# Sheet.net
KiCad netlist of a schematic drawn in Altium Designer
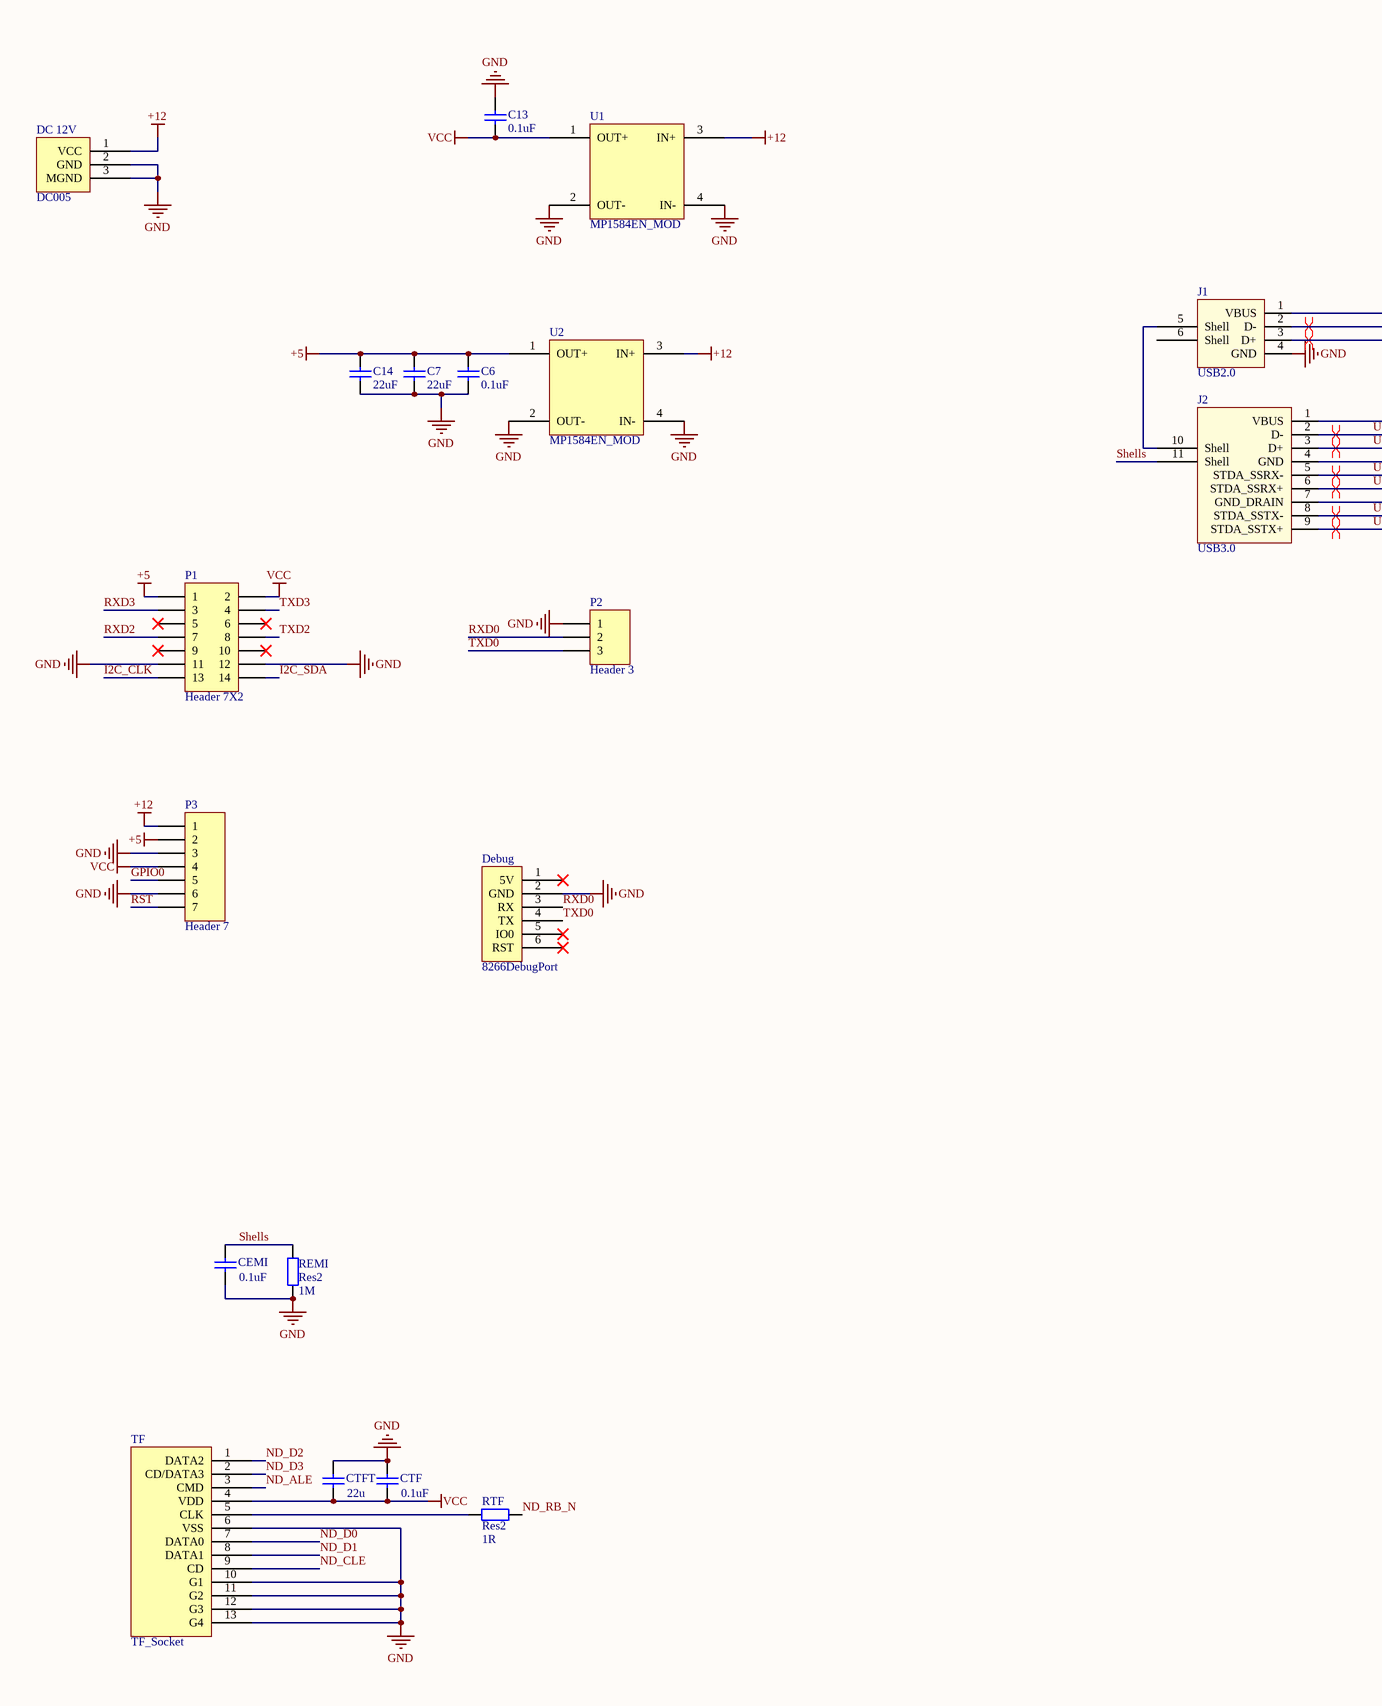
[diagram p0: Sheet.SchDoc, left]
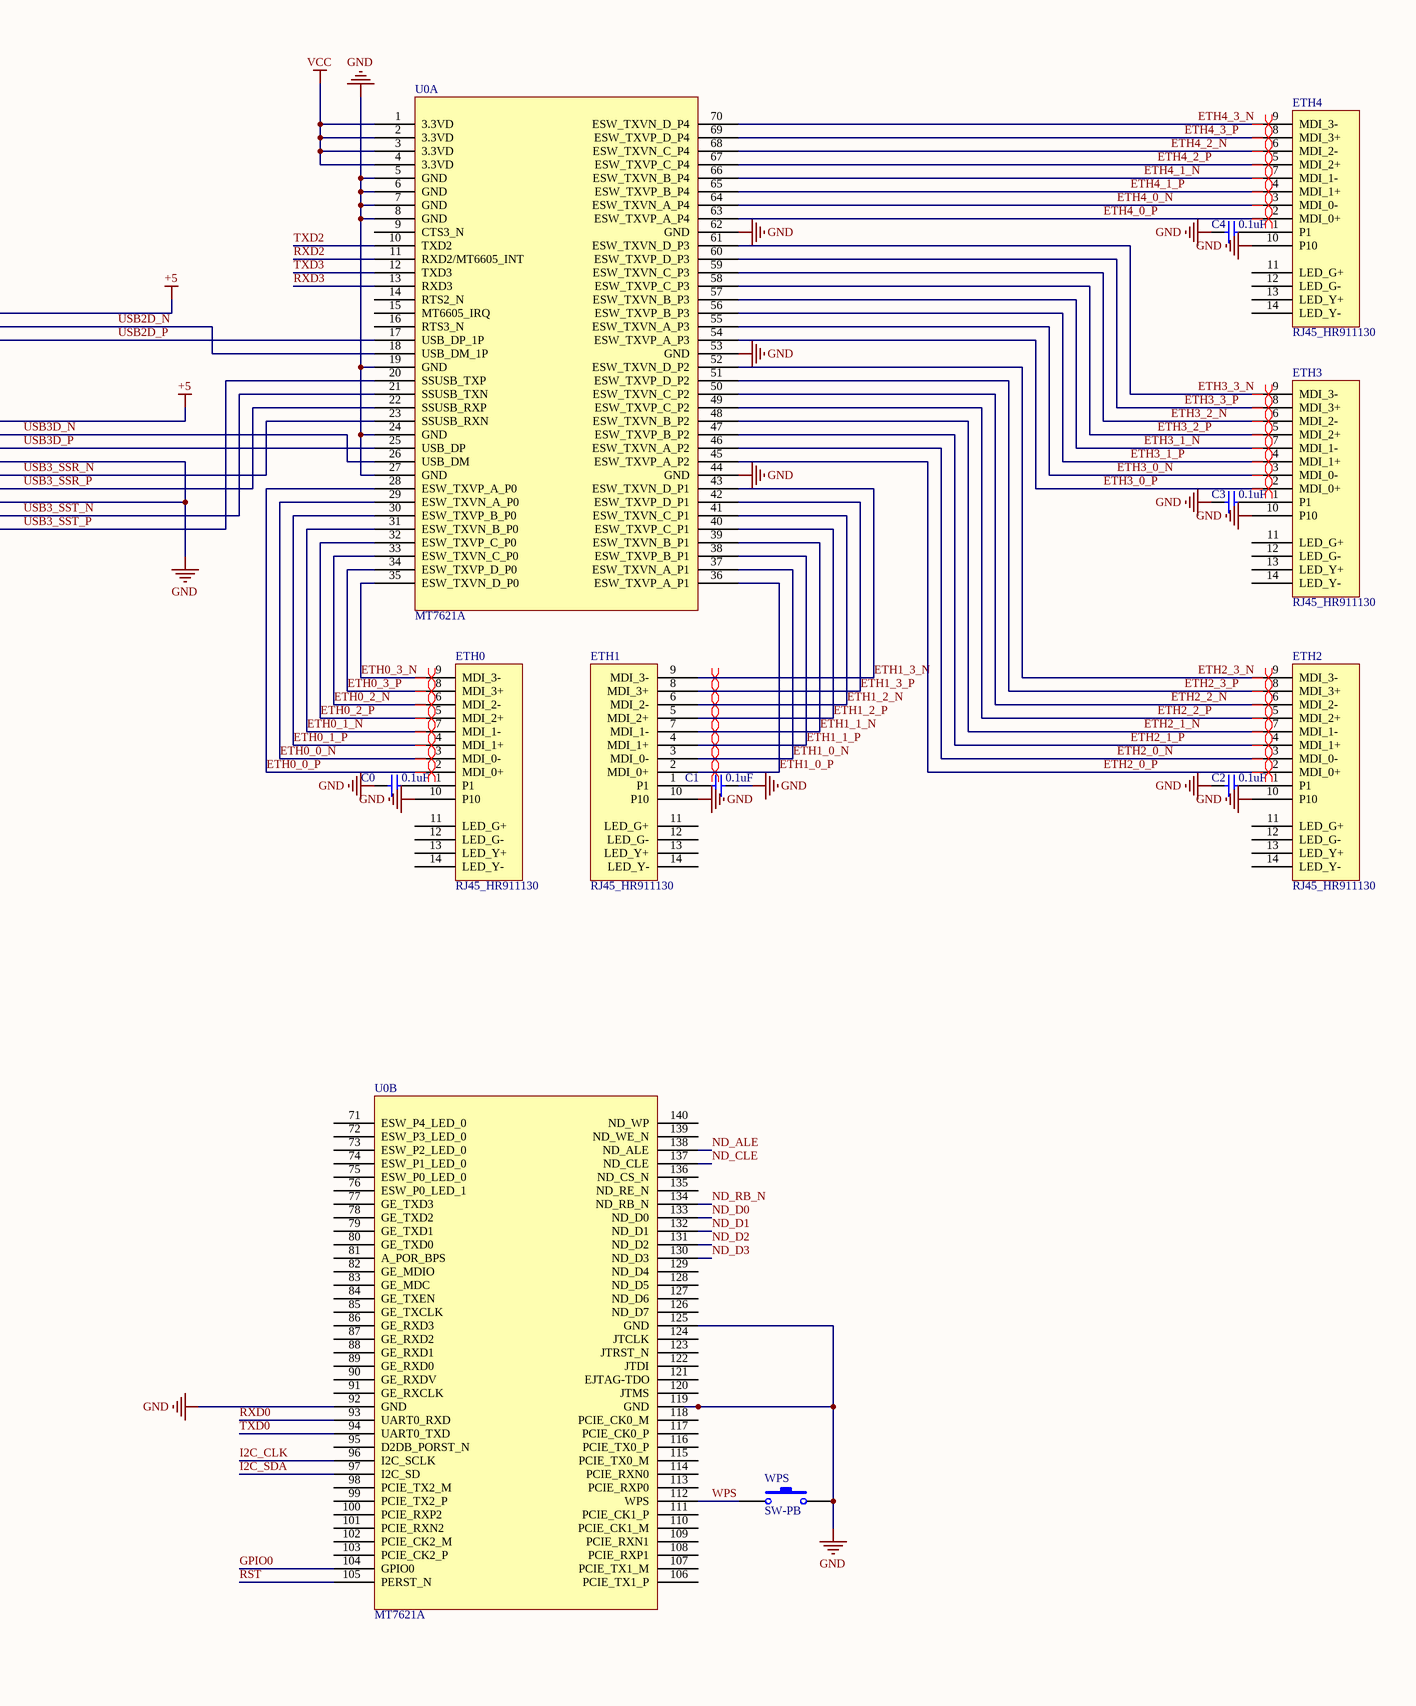
[diagram p1: Sheet.SchDoc, right]

(export (version "E")
  (design (tool "Eeschema 10.0.6"))
  (components
    (comp (ref "C0")
      (value "0.1uF")
      (footprint "My1206")
      (description "Capacitor")
      (fields (field (name "Comment") "Cap") (field (name "PUBLISHER") "Altium Limited"))
      (libsource (lib "Miscellaneous Devices") (part "Cap"))
    )
    (comp (ref "C1")
      (value "0.1uF")
      (footprint "My1206")
      (description "Capacitor")
      (fields (field (name "Comment") "Cap") (field (name "PUBLISHER") "Altium Limited"))
      (libsource (lib "Miscellaneous Devices") (part "Cap"))
    )
    (comp (ref "C2")
      (value "0.1uF")
      (footprint "My1206")
      (description "Capacitor")
      (fields (field (name "Comment") "Cap") (field (name "PUBLISHER") "Altium Limited"))
      (libsource (lib "Miscellaneous Devices") (part "Cap"))
    )
    (comp (ref "C3")
      (value "0.1uF")
      (footprint "My1206")
      (description "Capacitor")
      (fields (field (name "Comment") "Cap") (field (name "PUBLISHER") "Altium Limited"))
      (libsource (lib "Miscellaneous Devices") (part "Cap"))
    )
    (comp (ref "C4")
      (value "0.1uF")
      (footprint "My1206")
      (description "Capacitor")
      (fields (field (name "Comment") "Cap") (field (name "PUBLISHER") "Altium Limited"))
      (libsource (lib "Miscellaneous Devices") (part "Cap"))
    )
    (comp (ref "C6")
      (value "0.1uF")
      (footprint "My1206")
      (description "Capacitor")
      (fields (field (name "Comment") "Cap") (field (name "PUBLISHER") "Altium Limited"))
      (libsource (lib "Miscellaneous Devices") (part "Cap"))
    )
    (comp (ref "C7")
      (value "22uF")
      (footprint "My1206")
      (description "Capacitor")
      (fields (field (name "Comment") "Cap") (field (name "PUBLISHER") "Altium Limited"))
      (libsource (lib "Miscellaneous Devices") (part "Cap"))
    )
    (comp (ref "C13")
      (value "0.1uF")
      (footprint "My1206")
      (description "Capacitor")
      (fields (field (name "Comment") "Cap") (field (name "PUBLISHER") "Altium Limited"))
      (libsource (lib "Miscellaneous Devices") (part "Cap"))
    )
    (comp (ref "C14")
      (value "22uF")
      (footprint "My1206")
      (description "Capacitor")
      (fields (field (name "Comment") "Cap") (field (name "PUBLISHER") "Altium Limited"))
      (libsource (lib "Miscellaneous Devices") (part "Cap"))
    )
    (comp (ref "CEMI")
      (value "0.1uF")
      (footprint "My1206")
      (description "Capacitor")
      (fields (field (name "Comment") "Cap") (field (name "PUBLISHER") "Altium Limited"))
      (libsource (lib "Miscellaneous Devices") (part "Cap"))
    )
    (comp (ref "CTF")
      (value "0.1uF")
      (footprint "My1206")
      (description "Capacitor")
      (fields (field (name "Comment") "Cap") (field (name "PUBLISHER") "Altium Limited"))
      (libsource (lib "Miscellaneous Devices") (part "Cap"))
    )
    (comp (ref "CTFT")
      (value "22u")
      (footprint "My1206")
      (description "Capacitor")
      (fields (field (name "Comment") "Cap") (field (name "PUBLISHER") "Altium Limited"))
      (libsource (lib "Miscellaneous Devices") (part "Cap"))
    )
    (comp (ref "DC 12V") (value "DC005") (footprint "DC-005") (libsource (lib "我的元件库") (part "DC005")))
    (comp (ref "Debug")
      (value "8266DebugPort")
      (footprint "XH2.54-LI-6P")
      (libsource (lib "我的元件库") (part "8266DebugPort"))
    )
    (comp (ref "ETH0")
      (value "RJ45_HR911130")
      (footprint "RJ45_HR911130")
      (libsource (lib "7621_cmp") (part "RJ45_HR911130"))
    )
    (comp (ref "ETH1")
      (value "RJ45_HR911130")
      (footprint "RJ45_HR911130")
      (libsource (lib "") (part "RJ45_HR911130_1"))
    )
    (comp (ref "ETH2")
      (value "RJ45_HR911130")
      (footprint "RJ45_HR911130")
      (libsource (lib "7621_cmp") (part "RJ45_HR911130"))
    )
    (comp (ref "ETH3")
      (value "RJ45_HR911130")
      (footprint "RJ45_HR911130")
      (libsource (lib "7621_cmp") (part "RJ45_HR911130"))
    )
    (comp (ref "ETH4")
      (value "RJ45_HR911130")
      (footprint "RJ45_HR911130")
      (libsource (lib "7621_cmp") (part "RJ45_HR911130"))
    )
    (comp (ref "J1") (value "USB2.0") (footprint "USB2.0") (libsource (lib "7621_cmp") (part "USB2.0")))
    (comp (ref "J2") (value "USB3.0") (footprint "USB3.0_0") (libsource (lib "7621_cmp") (part "USB3.0")))
    (comp (ref "P1")
      (value "Header 7X2")
      (footprint "IDC3-7*2")
      (description "Header, 7-Pin, Dual row")
      (fields (field (name "PUBLISHER") "Altium Limited"))
      (libsource (lib "Miscellaneous Connectors") (part "Header 7X2"))
    )
    (comp (ref "P2")
      (value "Header 3")
      (footprint "HDR1X3")
      (description "Header, 3-Pin")
      (fields (field (name "PUBLISHER") "Altium Limited"))
      (libsource (lib "Miscellaneous Connectors") (part "Header 3"))
    )
    (comp (ref "P3")
      (value "Header 7")
      (footprint "XH2.54-LI-7P")
      (description "Header, 7-Pin")
      (fields (field (name "PUBLISHER") "Altium Limited"))
      (libsource (lib "Miscellaneous Connectors") (part "Header 7"))
    )
    (comp (ref "REMI")
      (value "Res2")
      (footprint "My1206")
      (description "Resistor")
      (fields (field (name "ALTIUM_VALUE") "1M") (field (name "PUBLISHER") "Altium Limited"))
      (libsource (lib "") (part "Res2_1"))
    )
    (comp (ref "RTF")
      (value "Res2")
      (footprint "My1206")
      (description "Resistor")
      (fields (field (name "ALTIUM_VALUE") "1R") (field (name "PUBLISHER") "Altium Limited"))
      (libsource (lib "Miscellaneous Devices") (part "Res2"))
    )
    (comp (ref "TF") (value "TF_Socket") (footprint "TF_Socket") (libsource (lib "我的元件库") (part "TF_Socket")))
    (comp (ref "U0") (value "MT7621A") (footprint "HLK7621") (libsource (lib "7621_cmp") (part "MT7621A")))
    (comp (ref "U1")
      (value "MP1584EN_MOD")
      (footprint "MP1584EN_MOD")
      (libsource (lib "7621_cmp") (part "MP1584EN_MOD"))
    )
    (comp (ref "U2")
      (value "MP1584EN_MOD")
      (footprint "MP1584EN_MOD")
      (libsource (lib "7621_cmp") (part "MP1584EN_MOD"))
    )
    (comp (ref "WPS")
      (value "SW-PB")
      (footprint "TSW SMD-3*6*2.5")
      (description "Switch")
      (fields (field (name "PUBLISHER") "Altium Limited"))
      (libsource (lib "Miscellaneous Devices") (part "SW-PB"))
    )
  )
  (nets
    (net (code "1") (name "+5") (class "Default")
      (node (ref "C14") (pin "1") (pinfunction "1_1") (pintype "passive"))
      (node (ref "C6") (pin "1") (pinfunction "1_1") (pintype "passive"))
      (node (ref "C7") (pin "1") (pinfunction "1_1") (pintype "passive"))
      (node (ref "J1") (pin "1") (pinfunction "VBUS_1") (pintype "passive"))
      (node (ref "J2") (pin "1") (pinfunction "VBUS_1") (pintype "passive"))
      (node (ref "P1") (pin "1") (pinfunction "1_1") (pintype "passive"))
      (node (ref "P3") (pin "2") (pinfunction "2_2") (pintype "passive"))
      (node (ref "U2") (pin "1") (pinfunction "OUT+_1") (pintype "passive"))
    )
    (net (code "2") (name "+12") (class "Default")
      (node (ref "DC 12V") (pin "1") (pinfunction "VCC_1") (pintype "passive"))
      (node (ref "P3") (pin "1") (pinfunction "1_1") (pintype "passive"))
      (node (ref "U1") (pin "3") (pinfunction "IN+_3") (pintype "passive"))
      (node (ref "U2") (pin "3") (pinfunction "IN+_3") (pintype "passive"))
    )
    (net (code "3") (name "/ETH0_0_N") (class "Default")
      (node (ref "ETH0") (pin "3") (pinfunction "MDI_0-_3") (pintype "passive"))
      (node (ref "U0") (pin "29") (pinfunction "ESW_TXVN_A_P0_29") (pintype "passive"))
    )
    (net (code "4") (name "/ETH0_0_P") (class "Default")
      (node (ref "ETH0") (pin "2") (pinfunction "MDI_0+_2") (pintype "passive"))
      (node (ref "U0") (pin "28") (pinfunction "ESW_TXVP_A_P0_28") (pintype "passive"))
    )
    (net (code "5") (name "/ETH0_1_N") (class "Default")
      (node (ref "ETH0") (pin "7") (pinfunction "MDI_1-_7") (pintype "passive"))
      (node (ref "U0") (pin "31") (pinfunction "ESW_TXVN_B_P0_31") (pintype "passive"))
    )
    (net (code "6") (name "/ETH0_1_P") (class "Default")
      (node (ref "ETH0") (pin "4") (pinfunction "MDI_1+_4") (pintype "passive"))
      (node (ref "U0") (pin "30") (pinfunction "ESW_TXVP_B_P0_30") (pintype "passive"))
    )
    (net (code "7") (name "/ETH0_2_N") (class "Default")
      (node (ref "ETH0") (pin "6") (pinfunction "MDI_2-_6") (pintype "passive"))
      (node (ref "U0") (pin "33") (pinfunction "ESW_TXVN_C_P0_33") (pintype "passive"))
    )
    (net (code "8") (name "/ETH0_2_P") (class "Default")
      (node (ref "ETH0") (pin "5") (pinfunction "MDI_2+_5") (pintype "passive"))
      (node (ref "U0") (pin "32") (pinfunction "ESW_TXVP_C_P0_32") (pintype "passive"))
    )
    (net (code "9") (name "/ETH0_3_N") (class "Default")
      (node (ref "ETH0") (pin "9") (pinfunction "MDI_3-_9") (pintype "passive"))
      (node (ref "U0") (pin "35") (pinfunction "ESW_TXVN_D_P0_35") (pintype "passive"))
    )
    (net (code "10") (name "/ETH0_3_P") (class "Default")
      (node (ref "ETH0") (pin "8") (pinfunction "MDI_3+_8") (pintype "passive"))
      (node (ref "U0") (pin "34") (pinfunction "ESW_TXVP_D_P0_34") (pintype "passive"))
    )
    (net (code "11") (name "/ETH1_0_N") (class "Default")
      (node (ref "ETH1") (pin "3") (pinfunction "MDI_0-_3") (pintype "passive"))
      (node (ref "U0") (pin "37") (pinfunction "ESW_TXVN_A_P1_37") (pintype "passive"))
    )
    (net (code "12") (name "/ETH1_0_P") (class "Default")
      (node (ref "ETH1") (pin "2") (pinfunction "MDI_0+_2") (pintype "passive"))
      (node (ref "U0") (pin "36") (pinfunction "ESW_TXVP_A_P1_36") (pintype "passive"))
    )
    (net (code "13") (name "/ETH1_1_N") (class "Default")
      (node (ref "ETH1") (pin "7") (pinfunction "MDI_1-_7") (pintype "passive"))
      (node (ref "U0") (pin "39") (pinfunction "ESW_TXVN_B_P1_39") (pintype "passive"))
    )
    (net (code "14") (name "/ETH1_1_P") (class "Default")
      (node (ref "ETH1") (pin "4") (pinfunction "MDI_1+_4") (pintype "passive"))
      (node (ref "U0") (pin "38") (pinfunction "ESW_TXVP_B_P1_38") (pintype "passive"))
    )
    (net (code "15") (name "/ETH1_2_N") (class "Default")
      (node (ref "ETH1") (pin "6") (pinfunction "MDI_2-_6") (pintype "passive"))
      (node (ref "U0") (pin "41") (pinfunction "ESW_TXVN_C_P1_41") (pintype "passive"))
    )
    (net (code "16") (name "/ETH1_2_P") (class "Default")
      (node (ref "ETH1") (pin "5") (pinfunction "MDI_2+_5") (pintype "passive"))
      (node (ref "U0") (pin "40") (pinfunction "ESW_TXVP_C_P1_40") (pintype "passive"))
    )
    (net (code "17") (name "/ETH1_3_N") (class "Default")
      (node (ref "ETH1") (pin "9") (pinfunction "MDI_3-_9") (pintype "passive"))
      (node (ref "U0") (pin "43") (pinfunction "ESW_TXVN_D_P1_43") (pintype "passive"))
    )
    (net (code "18") (name "/ETH1_3_P") (class "Default")
      (node (ref "ETH1") (pin "8") (pinfunction "MDI_3+_8") (pintype "passive"))
      (node (ref "U0") (pin "42") (pinfunction "ESW_TXVP_D_P1_42") (pintype "passive"))
    )
    (net (code "19") (name "/ETH2_0_N") (class "Default")
      (node (ref "ETH2") (pin "3") (pinfunction "MDI_0-_3") (pintype "passive"))
      (node (ref "U0") (pin "46") (pinfunction "ESW_TXVN_A_P2_46") (pintype "passive"))
    )
    (net (code "20") (name "/ETH2_0_P") (class "Default")
      (node (ref "ETH2") (pin "2") (pinfunction "MDI_0+_2") (pintype "passive"))
      (node (ref "U0") (pin "45") (pinfunction "ESW_TXVP_A_P2_45") (pintype "passive"))
    )
    (net (code "21") (name "/ETH2_1_N") (class "Default")
      (node (ref "ETH2") (pin "7") (pinfunction "MDI_1-_7") (pintype "passive"))
      (node (ref "U0") (pin "48") (pinfunction "ESW_TXVN_B_P2_48") (pintype "passive"))
    )
    (net (code "22") (name "/ETH2_1_P") (class "Default")
      (node (ref "ETH2") (pin "4") (pinfunction "MDI_1+_4") (pintype "passive"))
      (node (ref "U0") (pin "47") (pinfunction "ESW_TXVP_B_P2_47") (pintype "passive"))
    )
    (net (code "23") (name "/ETH2_2_N") (class "Default")
      (node (ref "ETH2") (pin "6") (pinfunction "MDI_2-_6") (pintype "passive"))
      (node (ref "U0") (pin "50") (pinfunction "ESW_TXVN_C_P2_50") (pintype "passive"))
    )
    (net (code "24") (name "/ETH2_2_P") (class "Default")
      (node (ref "ETH2") (pin "5") (pinfunction "MDI_2+_5") (pintype "passive"))
      (node (ref "U0") (pin "49") (pinfunction "ESW_TXVP_C_P2_49") (pintype "passive"))
    )
    (net (code "25") (name "/ETH2_3_N") (class "Default")
      (node (ref "ETH2") (pin "9") (pinfunction "MDI_3-_9") (pintype "passive"))
      (node (ref "U0") (pin "52") (pinfunction "ESW_TXVN_D_P2_52") (pintype "passive"))
    )
    (net (code "26") (name "/ETH2_3_P") (class "Default")
      (node (ref "ETH2") (pin "8") (pinfunction "MDI_3+_8") (pintype "passive"))
      (node (ref "U0") (pin "51") (pinfunction "ESW_TXVP_D_P2_51") (pintype "passive"))
    )
    (net (code "27") (name "/ETH3_0_N") (class "Default")
      (node (ref "ETH3") (pin "3") (pinfunction "MDI_0-_3") (pintype "passive"))
      (node (ref "U0") (pin "55") (pinfunction "ESW_TXVN_A_P3_55") (pintype "passive"))
    )
    (net (code "28") (name "/ETH3_0_P") (class "Default")
      (node (ref "ETH3") (pin "2") (pinfunction "MDI_0+_2") (pintype "passive"))
      (node (ref "U0") (pin "54") (pinfunction "ESW_TXVP_A_P3_54") (pintype "passive"))
    )
    (net (code "29") (name "/ETH3_1_N") (class "Default")
      (node (ref "ETH3") (pin "7") (pinfunction "MDI_1-_7") (pintype "passive"))
      (node (ref "U0") (pin "57") (pinfunction "ESW_TXVN_B_P3_57") (pintype "passive"))
    )
    (net (code "30") (name "/ETH3_1_P") (class "Default")
      (node (ref "ETH3") (pin "4") (pinfunction "MDI_1+_4") (pintype "passive"))
      (node (ref "U0") (pin "56") (pinfunction "ESW_TXVP_B_P3_56") (pintype "passive"))
    )
    (net (code "31") (name "/ETH3_2_N") (class "Default")
      (node (ref "ETH3") (pin "6") (pinfunction "MDI_2-_6") (pintype "passive"))
      (node (ref "U0") (pin "59") (pinfunction "ESW_TXVN_C_P3_59") (pintype "passive"))
    )
    (net (code "32") (name "/ETH3_2_P") (class "Default")
      (node (ref "ETH3") (pin "5") (pinfunction "MDI_2+_5") (pintype "passive"))
      (node (ref "U0") (pin "58") (pinfunction "ESW_TXVP_C_P3_58") (pintype "passive"))
    )
    (net (code "33") (name "/ETH3_3_N") (class "Default")
      (node (ref "ETH3") (pin "9") (pinfunction "MDI_3-_9") (pintype "passive"))
      (node (ref "U0") (pin "61") (pinfunction "ESW_TXVN_D_P3_61") (pintype "passive"))
    )
    (net (code "34") (name "/ETH3_3_P") (class "Default")
      (node (ref "ETH3") (pin "8") (pinfunction "MDI_3+_8") (pintype "passive"))
      (node (ref "U0") (pin "60") (pinfunction "ESW_TXVP_D_P3_60") (pintype "passive"))
    )
    (net (code "35") (name "/ETH4_0_N") (class "Default")
      (node (ref "ETH4") (pin "3") (pinfunction "MDI_0-_3") (pintype "passive"))
      (node (ref "U0") (pin "64") (pinfunction "ESW_TXVN_A_P4_64") (pintype "passive"))
    )
    (net (code "36") (name "/ETH4_0_P") (class "Default")
      (node (ref "ETH4") (pin "2") (pinfunction "MDI_0+_2") (pintype "passive"))
      (node (ref "U0") (pin "63") (pinfunction "ESW_TXVP_A_P4_63") (pintype "passive"))
    )
    (net (code "37") (name "/ETH4_1_N") (class "Default")
      (node (ref "ETH4") (pin "7") (pinfunction "MDI_1-_7") (pintype "passive"))
      (node (ref "U0") (pin "66") (pinfunction "ESW_TXVN_B_P4_66") (pintype "passive"))
    )
    (net (code "38") (name "/ETH4_1_P") (class "Default")
      (node (ref "ETH4") (pin "4") (pinfunction "MDI_1+_4") (pintype "passive"))
      (node (ref "U0") (pin "65") (pinfunction "ESW_TXVP_B_P4_65") (pintype "passive"))
    )
    (net (code "39") (name "/ETH4_2_N") (class "Default")
      (node (ref "ETH4") (pin "6") (pinfunction "MDI_2-_6") (pintype "passive"))
      (node (ref "U0") (pin "68") (pinfunction "ESW_TXVN_C_P4_68") (pintype "passive"))
    )
    (net (code "40") (name "/ETH4_2_P") (class "Default")
      (node (ref "ETH4") (pin "5") (pinfunction "MDI_2+_5") (pintype "passive"))
      (node (ref "U0") (pin "67") (pinfunction "ESW_TXVP_C_P4_67") (pintype "passive"))
    )
    (net (code "41") (name "/ETH4_3_N") (class "Default")
      (node (ref "ETH4") (pin "9") (pinfunction "MDI_3-_9") (pintype "passive"))
      (node (ref "U0") (pin "70") (pinfunction "ESW_TXVN_D_P4_70") (pintype "passive"))
    )
    (net (code "42") (name "/ETH4_3_P") (class "Default")
      (node (ref "ETH4") (pin "8") (pinfunction "MDI_3+_8") (pintype "passive"))
      (node (ref "U0") (pin "69") (pinfunction "ESW_TXVP_D_P4_69") (pintype "passive"))
    )
    (net (code "43") (name "/GPIO0") (class "Default")
      (node (ref "P3") (pin "5") (pinfunction "5_5") (pintype "passive"))
      (node (ref "U0") (pin "104") (pinfunction "GPIO0_104") (pintype "passive"))
    )
    (net (code "44") (name "/I2C_CLK") (class "Default")
      (node (ref "P1") (pin "13") (pinfunction "13_13") (pintype "passive"))
      (node (ref "U0") (pin "96") (pinfunction "I2C_SCLK_96") (pintype "passive"))
    )
    (net (code "45") (name "/I2C_SDA") (class "Default")
      (node (ref "P1") (pin "14") (pinfunction "14_14") (pintype "passive"))
      (node (ref "U0") (pin "97") (pinfunction "I2C_SD_97") (pintype "passive"))
    )
    (net (code "46") (name "/ND_ALE") (class "Default")
      (node (ref "TF") (pin "3") (pinfunction "CMD_3") (pintype "passive"))
      (node (ref "U0") (pin "138") (pinfunction "ND_ALE_138") (pintype "passive"))
    )
    (net (code "47") (name "/ND_CLE") (class "Default")
      (node (ref "TF") (pin "9") (pinfunction "CD_9") (pintype "passive"))
      (node (ref "U0") (pin "137") (pinfunction "ND_CLE_137") (pintype "passive"))
    )
    (net (code "48") (name "/ND_D0") (class "Default")
      (node (ref "TF") (pin "7") (pinfunction "DATA0_7") (pintype "passive"))
      (node (ref "U0") (pin "133") (pinfunction "ND_D0_133") (pintype "passive"))
    )
    (net (code "49") (name "/ND_D1") (class "Default")
      (node (ref "TF") (pin "8") (pinfunction "DATA1_8") (pintype "passive"))
      (node (ref "U0") (pin "132") (pinfunction "ND_D1_132") (pintype "passive"))
    )
    (net (code "50") (name "/ND_D2") (class "Default")
      (node (ref "TF") (pin "1") (pinfunction "DATA2_1") (pintype "passive"))
      (node (ref "U0") (pin "131") (pinfunction "ND_D2_131") (pintype "passive"))
    )
    (net (code "51") (name "/ND_D3") (class "Default")
      (node (ref "TF") (pin "2") (pinfunction "CD/DATA3_2") (pintype "passive"))
      (node (ref "U0") (pin "130") (pinfunction "ND_D3_130") (pintype "passive"))
    )
    (net (code "52") (name "/ND_RB_N") (class "Default")
      (node (ref "RTF") (pin "1") (pinfunction "1_1") (pintype "passive"))
      (node (ref "U0") (pin "134") (pinfunction "ND_RB_N_134") (pintype "passive"))
    )
    (net (code "53") (name "/RST") (class "Default")
      (node (ref "P3") (pin "7") (pinfunction "7_7") (pintype "passive"))
      (node (ref "U0") (pin "105") (pinfunction "PERST_N_105") (pintype "passive"))
    )
    (net (code "54") (name "/RXD0") (class "Default")
      (node (ref "Debug") (pin "3") (pinfunction "RX_3") (pintype "passive"))
      (node (ref "P2") (pin "2") (pinfunction "2_2") (pintype "passive"))
      (node (ref "U0") (pin "93") (pinfunction "UART0_RXD_93") (pintype "passive"))
    )
    (net (code "55") (name "/RXD2") (class "Default")
      (node (ref "P1") (pin "7") (pinfunction "7_7") (pintype "passive"))
      (node (ref "U0") (pin "11") (pinfunction "RXD2/MT6605_INT_11") (pintype "passive"))
    )
    (net (code "56") (name "/RXD3") (class "Default")
      (node (ref "P1") (pin "3") (pinfunction "3_3") (pintype "passive"))
      (node (ref "U0") (pin "13") (pinfunction "RXD3_13") (pintype "passive"))
    )
    (net (code "57") (name "/Shells") (class "Default")
      (node (ref "CEMI") (pin "2") (pinfunction "2_2") (pintype "passive"))
      (node (ref "J2") (pin "11") (pinfunction "Shell_11") (pintype "passive"))
      (node (ref "REMI") (pin "2") (pinfunction "2_2") (pintype "passive"))
    )
    (net (code "58") (name "/TXD0") (class "Default")
      (node (ref "Debug") (pin "4") (pinfunction "TX_4") (pintype "passive"))
      (node (ref "P2") (pin "3") (pinfunction "3_3") (pintype "passive"))
      (node (ref "U0") (pin "94") (pinfunction "UART0_TXD_94") (pintype "passive"))
    )
    (net (code "59") (name "/TXD2") (class "Default")
      (node (ref "P1") (pin "8") (pinfunction "8_8") (pintype "passive"))
      (node (ref "U0") (pin "10") (pinfunction "TXD2_10") (pintype "passive"))
    )
    (net (code "60") (name "/TXD3") (class "Default")
      (node (ref "P1") (pin "4") (pinfunction "4_4") (pintype "passive"))
      (node (ref "U0") (pin "12") (pinfunction "TXD3_12") (pintype "passive"))
    )
    (net (code "61") (name "/USB2D_N") (class "Default")
      (node (ref "J1") (pin "2") (pinfunction "D-_2") (pintype "passive"))
      (node (ref "U0") (pin "18") (pinfunction "USB_DM_1P_18") (pintype "passive"))
    )
    (net (code "62") (name "/USB2D_P") (class "Default")
      (node (ref "J1") (pin "3") (pinfunction "D+_3") (pintype "passive"))
      (node (ref "U0") (pin "17") (pinfunction "USB_DP_1P_17") (pintype "passive"))
    )
    (net (code "63") (name "/USB3D_N") (class "Default")
      (node (ref "J2") (pin "2") (pinfunction "D-_2") (pintype "passive"))
      (node (ref "U0") (pin "26") (pinfunction "USB_DM_26") (pintype "passive"))
    )
    (net (code "64") (name "/USB3D_P") (class "Default")
      (node (ref "J2") (pin "3") (pinfunction "D+_3") (pintype "passive"))
      (node (ref "U0") (pin "25") (pinfunction "USB_DP_25") (pintype "passive"))
    )
    (net (code "65") (name "/USB3_SSR_N") (class "Default")
      (node (ref "J2") (pin "5") (pinfunction "STDA_SSRX-_5") (pintype "passive"))
      (node (ref "U0") (pin "23") (pinfunction "SSUSB_RXN_23") (pintype "passive"))
    )
    (net (code "66") (name "/USB3_SSR_P") (class "Default")
      (node (ref "J2") (pin "6") (pinfunction "STDA_SSRX+_6") (pintype "passive"))
      (node (ref "U0") (pin "22") (pinfunction "SSUSB_RXP_22") (pintype "passive"))
    )
    (net (code "67") (name "/USB3_SST_N") (class "Default")
      (node (ref "J2") (pin "8") (pinfunction "STDA_SSTX-_8") (pintype "passive"))
      (node (ref "U0") (pin "21") (pinfunction "SSUSB_TXN_21") (pintype "passive"))
    )
    (net (code "68") (name "/USB3_SST_P") (class "Default")
      (node (ref "J2") (pin "9") (pinfunction "STDA_SSTX+_9") (pintype "passive"))
      (node (ref "U0") (pin "20") (pinfunction "SSUSB_TXP_20") (pintype "passive"))
    )
    (net (code "69") (name "/WPS") (class "Default")
      (node (ref "U0") (pin "112") (pinfunction "WPS_112") (pintype "passive"))
      (node (ref "WPS") (pin "1") (pinfunction "1_1") (pintype "passive"))
    )
    (net (code "70") (name "GND") (class "Default")
      (node (ref "C0") (pin "2") (pinfunction "2_2") (pintype "passive"))
      (node (ref "C1") (pin "1") (pinfunction "1_1") (pintype "passive"))
      (node (ref "C13") (pin "1") (pinfunction "1_1") (pintype "passive"))
      (node (ref "C14") (pin "2") (pinfunction "2_2") (pintype "passive"))
      (node (ref "C2") (pin "2") (pinfunction "2_2") (pintype "passive"))
      (node (ref "C3") (pin "2") (pinfunction "2_2") (pintype "passive"))
      (node (ref "C4") (pin "2") (pinfunction "2_2") (pintype "passive"))
      (node (ref "C6") (pin "2") (pinfunction "2_2") (pintype "passive"))
      (node (ref "C7") (pin "2") (pinfunction "2_2") (pintype "passive"))
      (node (ref "CEMI") (pin "1") (pinfunction "1_1") (pintype "passive"))
      (node (ref "CTF") (pin "2") (pinfunction "2_2") (pintype "passive"))
      (node (ref "CTFT") (pin "2") (pinfunction "2_2") (pintype "passive"))
      (node (ref "DC 12V") (pin "2") (pinfunction "GND_2") (pintype "passive"))
      (node (ref "DC 12V") (pin "3") (pinfunction "MGND_3") (pintype "passive"))
      (node (ref "Debug") (pin "2") (pinfunction "GND_2") (pintype "passive"))
      (node (ref "ETH0") (pin "10") (pinfunction "P10_10") (pintype "passive"))
      (node (ref "ETH1") (pin "10") (pinfunction "P10_10") (pintype "passive"))
      (node (ref "ETH2") (pin "10") (pinfunction "P10_10") (pintype "passive"))
      (node (ref "ETH3") (pin "10") (pinfunction "P10_10") (pintype "passive"))
      (node (ref "ETH4") (pin "10") (pinfunction "P10_10") (pintype "passive"))
      (node (ref "J1") (pin "4") (pinfunction "GND_4") (pintype "passive"))
      (node (ref "J2") (pin "4") (pinfunction "GND_4") (pintype "passive"))
      (node (ref "J2") (pin "7") (pinfunction "GND_DRAIN_7") (pintype "passive"))
      (node (ref "P1") (pin "11") (pinfunction "11_11") (pintype "passive"))
      (node (ref "P1") (pin "12") (pinfunction "12_12") (pintype "passive"))
      (node (ref "P2") (pin "1") (pinfunction "1_1") (pintype "passive"))
      (node (ref "P3") (pin "3") (pinfunction "3_3") (pintype "passive"))
      (node (ref "P3") (pin "6") (pinfunction "6_6") (pintype "passive"))
      (node (ref "REMI") (pin "1") (pinfunction "1_1") (pintype "passive"))
      (node (ref "TF") (pin "10") (pinfunction "G1_10") (pintype "passive"))
      (node (ref "TF") (pin "11") (pinfunction "G2_11") (pintype "passive"))
      (node (ref "TF") (pin "12") (pinfunction "G3_12") (pintype "passive"))
      (node (ref "TF") (pin "13") (pinfunction "G4_13") (pintype "passive"))
      (node (ref "TF") (pin "6") (pinfunction "VSS_6") (pintype "passive"))
      (node (ref "U0") (pin "119") (pinfunction "GND_119") (pintype "passive"))
      (node (ref "U0") (pin "125") (pinfunction "GND_125") (pintype "passive"))
      (node (ref "U0") (pin "19") (pinfunction "GND_19") (pintype "passive"))
      (node (ref "U0") (pin "24") (pinfunction "GND_24") (pintype "passive"))
      (node (ref "U0") (pin "27") (pinfunction "GND_27") (pintype "passive"))
      (node (ref "U0") (pin "44") (pinfunction "GND_44") (pintype "passive"))
      (node (ref "U0") (pin "5") (pinfunction "GND_5") (pintype "passive"))
      (node (ref "U0") (pin "53") (pinfunction "GND_53") (pintype "passive"))
      (node (ref "U0") (pin "6") (pinfunction "GND_6") (pintype "passive"))
      (node (ref "U0") (pin "62") (pinfunction "GND_62") (pintype "passive"))
      (node (ref "U0") (pin "7") (pinfunction "GND_7") (pintype "passive"))
      (node (ref "U0") (pin "8") (pinfunction "GND_8") (pintype "passive"))
      (node (ref "U0") (pin "92") (pinfunction "GND_92") (pintype "passive"))
      (node (ref "U1") (pin "2") (pinfunction "OUT-_2") (pintype "passive"))
      (node (ref "U1") (pin "4") (pinfunction "IN-_4") (pintype "passive"))
      (node (ref "U2") (pin "2") (pinfunction "OUT-_2") (pintype "passive"))
      (node (ref "U2") (pin "4") (pinfunction "IN-_4") (pintype "passive"))
      (node (ref "WPS") (pin "2") (pinfunction "2_2") (pintype "passive"))
    )
    (net (code "71") (name "Net-(ETH0-P1)") (class "Default")
      (node (ref "C0") (pin "1") (pinfunction "1_1") (pintype "passive"))
      (node (ref "ETH0") (pin "1") (pinfunction "P1_1") (pintype "passive"))
    )
    (net (code "72") (name "Net-(ETH1-P1)") (class "Default")
      (node (ref "C1") (pin "2") (pinfunction "2_2") (pintype "passive"))
      (node (ref "ETH1") (pin "1") (pinfunction "P1_1") (pintype "passive"))
    )
    (net (code "73") (name "Net-(ETH2-P1)") (class "Default")
      (node (ref "C2") (pin "1") (pinfunction "1_1") (pintype "passive"))
      (node (ref "ETH2") (pin "1") (pinfunction "P1_1") (pintype "passive"))
    )
    (net (code "74") (name "Net-(ETH3-P1)") (class "Default")
      (node (ref "C3") (pin "1") (pinfunction "1_1") (pintype "passive"))
      (node (ref "ETH3") (pin "1") (pinfunction "P1_1") (pintype "passive"))
    )
    (net (code "75") (name "Net-(ETH4-P1)") (class "Default")
      (node (ref "C4") (pin "1") (pinfunction "1_1") (pintype "passive"))
      (node (ref "ETH4") (pin "1") (pinfunction "P1_1") (pintype "passive"))
    )
    (net (code "76") (name "Net-(J1-Shell-Pad5)") (class "Default")
      (node (ref "J1") (pin "5") (pinfunction "Shell_5") (pintype "passive"))
      (node (ref "J2") (pin "10") (pinfunction "Shell_10") (pintype "passive"))
    )
    (net (code "77") (name "Net-(TF-CLK)") (class "Default")
      (node (ref "RTF") (pin "2") (pinfunction "2_2") (pintype "passive"))
      (node (ref "TF") (pin "5") (pinfunction "CLK_5") (pintype "passive"))
    )
    (net (code "78") (name "VCC") (class "Default")
      (node (ref "C13") (pin "2") (pinfunction "2_2") (pintype "passive"))
      (node (ref "CTF") (pin "1") (pinfunction "1_1") (pintype "passive"))
      (node (ref "CTFT") (pin "1") (pinfunction "1_1") (pintype "passive"))
      (node (ref "P1") (pin "2") (pinfunction "2_2") (pintype "passive"))
      (node (ref "P3") (pin "4") (pinfunction "4_4") (pintype "passive"))
      (node (ref "TF") (pin "4") (pinfunction "VDD_4") (pintype "passive"))
      (node (ref "U0") (pin "1") (pinfunction "3.3VD_1") (pintype "passive"))
      (node (ref "U0") (pin "2") (pinfunction "3.3VD_2") (pintype "passive"))
      (node (ref "U0") (pin "3") (pinfunction "3.3VD_3") (pintype "passive"))
      (node (ref "U0") (pin "4") (pinfunction "3.3VD_4") (pintype "passive"))
      (node (ref "U1") (pin "1") (pinfunction "OUT+_1") (pintype "passive"))
    )
    (net (code "79") (name "unconnected-(Debug-5V-Pad1)") (class "Default")
      (node (ref "Debug") (pin "1") (pinfunction "5V_1") (pintype "passive+no_connect"))
    )
    (net (code "80") (name "unconnected-(Debug-IO0-Pad5)") (class "Default")
      (node (ref "Debug") (pin "5") (pinfunction "IO0_5") (pintype "passive+no_connect"))
    )
    (net (code "81") (name "unconnected-(Debug-RST-Pad6)") (class "Default")
      (node (ref "Debug") (pin "6") (pinfunction "RST_6") (pintype "passive+no_connect"))
    )
    (net (code "82") (name "unconnected-(ETH0-LED_G+-Pad11)") (class "Default")
      (node (ref "ETH0") (pin "11") (pinfunction "LED_G+_11") (pintype "passive"))
    )
    (net (code "83") (name "unconnected-(ETH0-LED_G--Pad12)") (class "Default")
      (node (ref "ETH0") (pin "12") (pinfunction "LED_G-_12") (pintype "passive"))
    )
    (net (code "84") (name "unconnected-(ETH0-LED_Y+-Pad13)") (class "Default")
      (node (ref "ETH0") (pin "13") (pinfunction "LED_Y+_13") (pintype "passive"))
    )
    (net (code "85") (name "unconnected-(ETH0-LED_Y--Pad14)") (class "Default")
      (node (ref "ETH0") (pin "14") (pinfunction "LED_Y-_14") (pintype "passive"))
    )
    (net (code "86") (name "unconnected-(ETH1-LED_G+-Pad11)") (class "Default")
      (node (ref "ETH1") (pin "11") (pinfunction "LED_G+_11") (pintype "passive"))
    )
    (net (code "87") (name "unconnected-(ETH1-LED_G--Pad12)") (class "Default")
      (node (ref "ETH1") (pin "12") (pinfunction "LED_G-_12") (pintype "passive"))
    )
    (net (code "88") (name "unconnected-(ETH1-LED_Y+-Pad13)") (class "Default")
      (node (ref "ETH1") (pin "13") (pinfunction "LED_Y+_13") (pintype "passive"))
    )
    (net (code "89") (name "unconnected-(ETH1-LED_Y--Pad14)") (class "Default")
      (node (ref "ETH1") (pin "14") (pinfunction "LED_Y-_14") (pintype "passive"))
    )
    (net (code "90") (name "unconnected-(ETH2-LED_G+-Pad11)") (class "Default")
      (node (ref "ETH2") (pin "11") (pinfunction "LED_G+_11") (pintype "passive"))
    )
    (net (code "91") (name "unconnected-(ETH2-LED_G--Pad12)") (class "Default")
      (node (ref "ETH2") (pin "12") (pinfunction "LED_G-_12") (pintype "passive"))
    )
    (net (code "92") (name "unconnected-(ETH2-LED_Y+-Pad13)") (class "Default")
      (node (ref "ETH2") (pin "13") (pinfunction "LED_Y+_13") (pintype "passive"))
    )
    (net (code "93") (name "unconnected-(ETH2-LED_Y--Pad14)") (class "Default")
      (node (ref "ETH2") (pin "14") (pinfunction "LED_Y-_14") (pintype "passive"))
    )
    (net (code "94") (name "unconnected-(ETH3-LED_G+-Pad11)") (class "Default")
      (node (ref "ETH3") (pin "11") (pinfunction "LED_G+_11") (pintype "passive"))
    )
    (net (code "95") (name "unconnected-(ETH3-LED_G--Pad12)") (class "Default")
      (node (ref "ETH3") (pin "12") (pinfunction "LED_G-_12") (pintype "passive"))
    )
    (net (code "96") (name "unconnected-(ETH3-LED_Y+-Pad13)") (class "Default")
      (node (ref "ETH3") (pin "13") (pinfunction "LED_Y+_13") (pintype "passive"))
    )
    (net (code "97") (name "unconnected-(ETH3-LED_Y--Pad14)") (class "Default")
      (node (ref "ETH3") (pin "14") (pinfunction "LED_Y-_14") (pintype "passive"))
    )
    (net (code "98") (name "unconnected-(ETH4-LED_G+-Pad11)") (class "Default")
      (node (ref "ETH4") (pin "11") (pinfunction "LED_G+_11") (pintype "passive"))
    )
    (net (code "99") (name "unconnected-(ETH4-LED_G--Pad12)") (class "Default")
      (node (ref "ETH4") (pin "12") (pinfunction "LED_G-_12") (pintype "passive"))
    )
    (net (code "100") (name "unconnected-(ETH4-LED_Y+-Pad13)") (class "Default")
      (node (ref "ETH4") (pin "13") (pinfunction "LED_Y+_13") (pintype "passive"))
    )
    (net (code "101") (name "unconnected-(ETH4-LED_Y--Pad14)") (class "Default")
      (node (ref "ETH4") (pin "14") (pinfunction "LED_Y-_14") (pintype "passive"))
    )
    (net (code "102") (name "unconnected-(J1-Shell-Pad6)") (class "Default")
      (node (ref "J1") (pin "6") (pinfunction "Shell_6") (pintype "passive"))
    )
    (net (code "103") (name "unconnected-(P1-Pad5)") (class "Default")
      (node (ref "P1") (pin "5") (pinfunction "5_5") (pintype "passive+no_connect"))
    )
    (net (code "104") (name "unconnected-(P1-Pad6)") (class "Default")
      (node (ref "P1") (pin "6") (pinfunction "6_6") (pintype "passive+no_connect"))
    )
    (net (code "105") (name "unconnected-(P1-Pad9)") (class "Default")
      (node (ref "P1") (pin "9") (pinfunction "9_9") (pintype "passive+no_connect"))
    )
    (net (code "106") (name "unconnected-(P1-Pad10)") (class "Default")
      (node (ref "P1") (pin "10") (pinfunction "10_10") (pintype "passive+no_connect"))
    )
    (net (code "107") (name "unconnected-(U0A-CTS3_N-Pad9)") (class "Default")
      (node (ref "U0") (pin "9") (pinfunction "CTS3_N_9") (pintype "passive"))
    )
    (net (code "108") (name "unconnected-(U0A-MT6605_IRQ-Pad15)") (class "Default")
      (node (ref "U0") (pin "15") (pinfunction "MT6605_IRQ_15") (pintype "passive"))
    )
    (net (code "109") (name "unconnected-(U0A-RTS2_N-Pad14)") (class "Default")
      (node (ref "U0") (pin "14") (pinfunction "RTS2_N_14") (pintype "passive"))
    )
    (net (code "110") (name "unconnected-(U0A-RTS3_N-Pad16)") (class "Default")
      (node (ref "U0") (pin "16") (pinfunction "RTS3_N_16") (pintype "passive"))
    )
    (net (code "111") (name "unconnected-(U0B-A_POR_BPS-Pad81)") (class "Default")
      (node (ref "U0") (pin "81") (pinfunction "A_POR_BPS_81") (pintype "passive"))
    )
    (net (code "112") (name "unconnected-(U0B-D2DB_PORST_N-Pad95)") (class "Default")
      (node (ref "U0") (pin "95") (pinfunction "D2DB_PORST_N_95") (pintype "passive"))
    )
    (net (code "113") (name "unconnected-(U0B-EJTAG-TDO-Pad121)") (class "Default")
      (node (ref "U0") (pin "121") (pinfunction "EJTAG-TDO_121") (pintype "passive"))
    )
    (net (code "114") (name "unconnected-(U0B-ESW_P0_LED_0-Pad75)") (class "Default")
      (node (ref "U0") (pin "75") (pinfunction "ESW_P0_LED_0_75") (pintype "passive"))
    )
    (net (code "115") (name "unconnected-(U0B-ESW_P0_LED_1-Pad76)") (class "Default")
      (node (ref "U0") (pin "76") (pinfunction "ESW_P0_LED_1_76") (pintype "passive"))
    )
    (net (code "116") (name "unconnected-(U0B-ESW_P1_LED_0-Pad74)") (class "Default")
      (node (ref "U0") (pin "74") (pinfunction "ESW_P1_LED_0_74") (pintype "passive"))
    )
    (net (code "117") (name "unconnected-(U0B-ESW_P2_LED_0-Pad73)") (class "Default")
      (node (ref "U0") (pin "73") (pinfunction "ESW_P2_LED_0_73") (pintype "passive"))
    )
    (net (code "118") (name "unconnected-(U0B-ESW_P3_LED_0-Pad72)") (class "Default")
      (node (ref "U0") (pin "72") (pinfunction "ESW_P3_LED_0_72") (pintype "passive"))
    )
    (net (code "119") (name "unconnected-(U0B-ESW_P4_LED_0-Pad71)") (class "Default")
      (node (ref "U0") (pin "71") (pinfunction "ESW_P4_LED_0_71") (pintype "passive"))
    )
    (net (code "120") (name "unconnected-(U0B-GE_MDC-Pad83)") (class "Default")
      (node (ref "U0") (pin "83") (pinfunction "GE_MDC_83") (pintype "passive"))
    )
    (net (code "121") (name "unconnected-(U0B-GE_MDIO-Pad82)") (class "Default")
      (node (ref "U0") (pin "82") (pinfunction "GE_MDIO_82") (pintype "passive"))
    )
    (net (code "122") (name "unconnected-(U0B-GE_RXCLK-Pad91)") (class "Default")
      (node (ref "U0") (pin "91") (pinfunction "GE_RXCLK_91") (pintype "passive"))
    )
    (net (code "123") (name "unconnected-(U0B-GE_RXD0-Pad89)") (class "Default")
      (node (ref "U0") (pin "89") (pinfunction "GE_RXD0_89") (pintype "passive"))
    )
    (net (code "124") (name "unconnected-(U0B-GE_RXD1-Pad88)") (class "Default")
      (node (ref "U0") (pin "88") (pinfunction "GE_RXD1_88") (pintype "passive"))
    )
    (net (code "125") (name "unconnected-(U0B-GE_RXD2-Pad87)") (class "Default")
      (node (ref "U0") (pin "87") (pinfunction "GE_RXD2_87") (pintype "passive"))
    )
    (net (code "126") (name "unconnected-(U0B-GE_RXD3-Pad86)") (class "Default")
      (node (ref "U0") (pin "86") (pinfunction "GE_RXD3_86") (pintype "passive"))
    )
    (net (code "127") (name "unconnected-(U0B-GE_RXDV-Pad90)") (class "Default")
      (node (ref "U0") (pin "90") (pinfunction "GE_RXDV_90") (pintype "passive"))
    )
    (net (code "128") (name "unconnected-(U0B-GE_TXCLK-Pad85)") (class "Default")
      (node (ref "U0") (pin "85") (pinfunction "GE_TXCLK_85") (pintype "passive"))
    )
    (net (code "129") (name "unconnected-(U0B-GE_TXD0-Pad80)") (class "Default")
      (node (ref "U0") (pin "80") (pinfunction "GE_TXD0_80") (pintype "passive"))
    )
    (net (code "130") (name "unconnected-(U0B-GE_TXD1-Pad79)") (class "Default")
      (node (ref "U0") (pin "79") (pinfunction "GE_TXD1_79") (pintype "passive"))
    )
    (net (code "131") (name "unconnected-(U0B-GE_TXD2-Pad78)") (class "Default")
      (node (ref "U0") (pin "78") (pinfunction "GE_TXD2_78") (pintype "passive"))
    )
    (net (code "132") (name "unconnected-(U0B-GE_TXD3-Pad77)") (class "Default")
      (node (ref "U0") (pin "77") (pinfunction "GE_TXD3_77") (pintype "passive"))
    )
    (net (code "133") (name "unconnected-(U0B-GE_TXEN-Pad84)") (class "Default")
      (node (ref "U0") (pin "84") (pinfunction "GE_TXEN_84") (pintype "passive"))
    )
    (net (code "134") (name "unconnected-(U0B-JTCLK-Pad124)") (class "Default")
      (node (ref "U0") (pin "124") (pinfunction "JTCLK_124") (pintype "passive"))
    )
    (net (code "135") (name "unconnected-(U0B-JTDI-Pad122)") (class "Default")
      (node (ref "U0") (pin "122") (pinfunction "JTDI_122") (pintype "passive"))
    )
    (net (code "136") (name "unconnected-(U0B-JTMS-Pad120)") (class "Default")
      (node (ref "U0") (pin "120") (pinfunction "JTMS_120") (pintype "passive"))
    )
    (net (code "137") (name "unconnected-(U0B-JTRST_N-Pad123)") (class "Default")
      (node (ref "U0") (pin "123") (pinfunction "JTRST_N_123") (pintype "passive"))
    )
    (net (code "138") (name "unconnected-(U0B-ND_CS_N-Pad136)") (class "Default")
      (node (ref "U0") (pin "136") (pinfunction "ND_CS_N_136") (pintype "passive"))
    )
    (net (code "139") (name "unconnected-(U0B-ND_D4-Pad129)") (class "Default")
      (node (ref "U0") (pin "129") (pinfunction "ND_D4_129") (pintype "passive"))
    )
    (net (code "140") (name "unconnected-(U0B-ND_D5-Pad128)") (class "Default")
      (node (ref "U0") (pin "128") (pinfunction "ND_D5_128") (pintype "passive"))
    )
    (net (code "141") (name "unconnected-(U0B-ND_D6-Pad127)") (class "Default")
      (node (ref "U0") (pin "127") (pinfunction "ND_D6_127") (pintype "passive"))
    )
    (net (code "142") (name "unconnected-(U0B-ND_D7-Pad126)") (class "Default")
      (node (ref "U0") (pin "126") (pinfunction "ND_D7_126") (pintype "passive"))
    )
    (net (code "143") (name "unconnected-(U0B-ND_RE_N-Pad135)") (class "Default")
      (node (ref "U0") (pin "135") (pinfunction "ND_RE_N_135") (pintype "passive"))
    )
    (net (code "144") (name "unconnected-(U0B-ND_WE_N-Pad139)") (class "Default")
      (node (ref "U0") (pin "139") (pinfunction "ND_WE_N_139") (pintype "passive"))
    )
    (net (code "145") (name "unconnected-(U0B-ND_WP-Pad140)") (class "Default")
      (node (ref "U0") (pin "140") (pinfunction "ND_WP_140") (pintype "passive"))
    )
    (net (code "146") (name "unconnected-(U0B-PCIE_CK0_M-Pad118)") (class "Default")
      (node (ref "U0") (pin "118") (pinfunction "PCIE_CK0_M_118") (pintype "passive"))
    )
    (net (code "147") (name "unconnected-(U0B-PCIE_CK0_P-Pad117)") (class "Default")
      (node (ref "U0") (pin "117") (pinfunction "PCIE_CK0_P_117") (pintype "passive"))
    )
    (net (code "148") (name "unconnected-(U0B-PCIE_CK1_M-Pad110)") (class "Default")
      (node (ref "U0") (pin "110") (pinfunction "PCIE_CK1_M_110") (pintype "passive"))
    )
    (net (code "149") (name "unconnected-(U0B-PCIE_CK1_P-Pad111)") (class "Default")
      (node (ref "U0") (pin "111") (pinfunction "PCIE_CK1_P_111") (pintype "passive"))
    )
    (net (code "150") (name "unconnected-(U0B-PCIE_CK2_M-Pad102)") (class "Default")
      (node (ref "U0") (pin "102") (pinfunction "PCIE_CK2_M_102") (pintype "passive"))
    )
    (net (code "151") (name "unconnected-(U0B-PCIE_CK2_P-Pad103)") (class "Default")
      (node (ref "U0") (pin "103") (pinfunction "PCIE_CK2_P_103") (pintype "passive"))
    )
    (net (code "152") (name "unconnected-(U0B-PCIE_RXN0-Pad114)") (class "Default")
      (node (ref "U0") (pin "114") (pinfunction "PCIE_RXN0_114") (pintype "passive"))
    )
    (net (code "153") (name "unconnected-(U0B-PCIE_RXN1-Pad109)") (class "Default")
      (node (ref "U0") (pin "109") (pinfunction "PCIE_RXN1_109") (pintype "passive"))
    )
    (net (code "154") (name "unconnected-(U0B-PCIE_RXN2-Pad101)") (class "Default")
      (node (ref "U0") (pin "101") (pinfunction "PCIE_RXN2_101") (pintype "passive"))
    )
    (net (code "155") (name "unconnected-(U0B-PCIE_RXP0-Pad113)") (class "Default")
      (node (ref "U0") (pin "113") (pinfunction "PCIE_RXP0_113") (pintype "passive"))
    )
    (net (code "156") (name "unconnected-(U0B-PCIE_RXP1-Pad108)") (class "Default")
      (node (ref "U0") (pin "108") (pinfunction "PCIE_RXP1_108") (pintype "passive"))
    )
    (net (code "157") (name "unconnected-(U0B-PCIE_RXP2-Pad100)") (class "Default")
      (node (ref "U0") (pin "100") (pinfunction "PCIE_RXP2_100") (pintype "passive"))
    )
    (net (code "158") (name "unconnected-(U0B-PCIE_TX0_M-Pad115)") (class "Default")
      (node (ref "U0") (pin "115") (pinfunction "PCIE_TX0_M_115") (pintype "passive"))
    )
    (net (code "159") (name "unconnected-(U0B-PCIE_TX0_P-Pad116)") (class "Default")
      (node (ref "U0") (pin "116") (pinfunction "PCIE_TX0_P_116") (pintype "passive"))
    )
    (net (code "160") (name "unconnected-(U0B-PCIE_TX1_M-Pad107)") (class "Default")
      (node (ref "U0") (pin "107") (pinfunction "PCIE_TX1_M_107") (pintype "passive"))
    )
    (net (code "161") (name "unconnected-(U0B-PCIE_TX1_P-Pad106)") (class "Default")
      (node (ref "U0") (pin "106") (pinfunction "PCIE_TX1_P_106") (pintype "passive"))
    )
    (net (code "162") (name "unconnected-(U0B-PCIE_TX2_M-Pad98)") (class "Default")
      (node (ref "U0") (pin "98") (pinfunction "PCIE_TX2_M_98") (pintype "passive"))
    )
    (net (code "163") (name "unconnected-(U0B-PCIE_TX2_P-Pad99)") (class "Default")
      (node (ref "U0") (pin "99") (pinfunction "PCIE_TX2_P_99") (pintype "passive"))
    )
  )
)
